# PMB.net
KiCad netlist of a schematic drawn in EAGLE
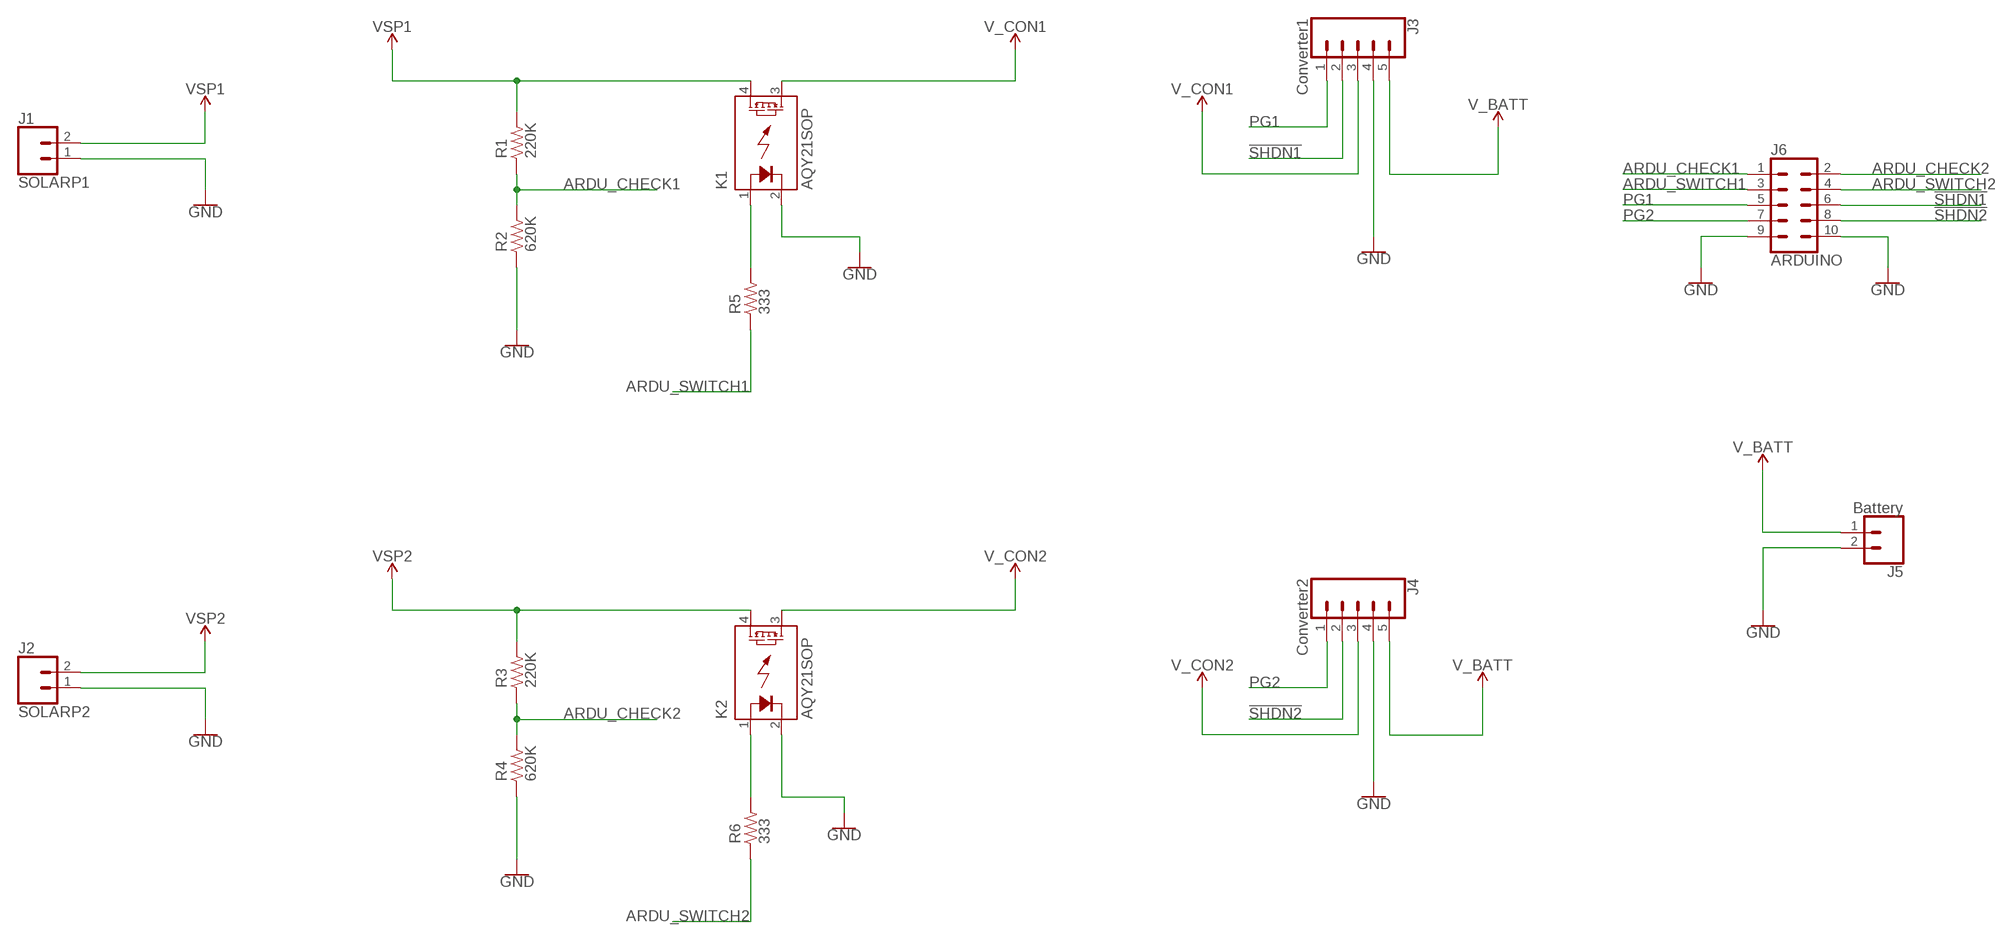
[diagram p0: schematic, sheet 1]

(export (version "E")
  (design (tool "Eeschema 10.0.6"))
  (components
    (comp (ref "J1")
      (value "SOLARP1")
      (footprint "eagle-import:1X02_LONGPADS")
      (libsource (lib "eagle-import") (part "CONN_02PTH3"))
    )
    (comp (ref "J2")
      (value "SOLARP2")
      (footprint "eagle-import:1X02_LONGPADS")
      (libsource (lib "eagle-import") (part "CONN_02PTH3"))
    )
    (comp (ref "J3")
      (value "Converter1")
      (footprint "eagle-import:1X05_LONGPADS")
      (libsource (lib "eagle-import") (part "CONN_05PTH_LONGPADS"))
    )
    (comp (ref "J4")
      (value "Converter2")
      (footprint "eagle-import:1X05_LONGPADS")
      (libsource (lib "eagle-import") (part "CONN_05PTH_LONGPADS"))
    )
    (comp (ref "J5")
      (value "Battery")
      (footprint "eagle-import:1X02_LOCK_LONGPADS")
      (libsource (lib "eagle-import") (part "CONN_02LOCK_LONGPADS"))
    )
    (comp (ref "J6")
      (value "ARDUINO")
      (footprint "eagle-import:2X5")
      (libsource (lib "eagle-import") (part "CONN_05X2PTH"))
    )
    (comp (ref "K1")
      (value "AQY21SOP")
      (footprint "eagle-import:SOP04")
      (libsource (lib "eagle-import") (part "AQYSOP21"))
    )
    (comp (ref "K2")
      (value "AQY21SOP")
      (footprint "eagle-import:SOP04")
      (libsource (lib "eagle-import") (part "AQYSOP21"))
    )
    (comp (ref "R1")
      (value "220K")
      (footprint "eagle-import:R1206")
      (libsource (lib "eagle-import") (part "R_1206"))
    )
    (comp (ref "R2")
      (value "620K")
      (footprint "eagle-import:R1206")
      (libsource (lib "eagle-import") (part "R_1206"))
    )
    (comp (ref "R3")
      (value "220K")
      (footprint "eagle-import:R1206")
      (libsource (lib "eagle-import") (part "R_1206"))
    )
    (comp (ref "R4")
      (value "620K")
      (footprint "eagle-import:R1206")
      (libsource (lib "eagle-import") (part "R_1206"))
    )
    (comp (ref "R5")
      (value "333")
      (footprint "eagle-import:R1206")
      (libsource (lib "eagle-import") (part "R_1206"))
    )
    (comp (ref "R6")
      (value "333")
      (footprint "eagle-import:R1206")
      (libsource (lib "eagle-import") (part "R_1206"))
    )
  )
  (nets
    (net (code "1") (name "/ARDU_CHECK1") (class "Default")
      (node (ref "J6") (pin "1") (pinfunction "1_1") (pintype "passive"))
      (node (ref "R1") (pin "1") (pinfunction "1_1") (pintype "passive"))
      (node (ref "R2") (pin "2") (pinfunction "2_2") (pintype "passive"))
    )
    (net (code "2") (name "/ARDU_CHECK2") (class "Default")
      (node (ref "J6") (pin "2") (pinfunction "2_2") (pintype "passive"))
      (node (ref "R3") (pin "1") (pinfunction "1_1") (pintype "passive"))
      (node (ref "R4") (pin "2") (pinfunction "2_2") (pintype "passive"))
    )
    (net (code "3") (name "/ARDU_SWITCH1") (class "Default")
      (node (ref "J6") (pin "3") (pinfunction "3_3") (pintype "passive"))
      (node (ref "R5") (pin "1") (pinfunction "1_1") (pintype "passive"))
    )
    (net (code "4") (name "/ARDU_SWITCH2") (class "Default")
      (node (ref "J6") (pin "4") (pinfunction "4_4") (pintype "passive"))
      (node (ref "R6") (pin "1") (pinfunction "1_1") (pintype "passive"))
    )
    (net (code "5") (name "/N$1") (class "Default")
      (node (ref "K1") (pin "1") (pinfunction "A_1") (pintype "passive"))
      (node (ref "K2") (pin "1") (pinfunction "A_1") (pintype "passive"))
      (node (ref "R5") (pin "2") (pinfunction "2_2") (pintype "passive"))
      (node (ref "R6") (pin "2") (pinfunction "2_2") (pintype "passive"))
    )
    (net (code "6") (name "/PG1") (class "Default")
      (node (ref "J3") (pin "1") (pinfunction "1_1") (pintype "passive"))
      (node (ref "J6") (pin "5") (pinfunction "5_5") (pintype "passive"))
    )
    (net (code "7") (name "/PG2") (class "Default")
      (node (ref "J4") (pin "1") (pinfunction "1_1") (pintype "passive"))
      (node (ref "J6") (pin "7") (pinfunction "7_7") (pintype "passive"))
    )
    (net (code "8") (name "/~{SHDN1}") (class "Default")
      (node (ref "J3") (pin "2") (pinfunction "2_2") (pintype "passive"))
      (node (ref "J6") (pin "6") (pinfunction "6_6") (pintype "passive"))
    )
    (net (code "9") (name "/~{SHDN2}") (class "Default")
      (node (ref "J4") (pin "2") (pinfunction "2_2") (pintype "passive"))
      (node (ref "J6") (pin "8") (pinfunction "8_8") (pintype "passive"))
    )
    (net (code "10") (name "GND") (class "Default")
      (node (ref "J1") (pin "1") (pinfunction "1_1") (pintype "passive"))
      (node (ref "J2") (pin "1") (pinfunction "1_1") (pintype "passive"))
      (node (ref "J3") (pin "4") (pinfunction "4_4") (pintype "passive"))
      (node (ref "J4") (pin "4") (pinfunction "4_4") (pintype "passive"))
      (node (ref "J5") (pin "2") (pinfunction "2_2") (pintype "passive"))
      (node (ref "J6") (pin "10") (pinfunction "10_10") (pintype "passive"))
      (node (ref "J6") (pin "9") (pinfunction "9_9") (pintype "passive"))
      (node (ref "K1") (pin "2") (pinfunction "K_2") (pintype "passive"))
      (node (ref "K2") (pin "2") (pinfunction "K_2") (pintype "passive"))
      (node (ref "R2") (pin "1") (pinfunction "1_1") (pintype "passive"))
      (node (ref "R4") (pin "1") (pinfunction "1_1") (pintype "passive"))
    )
    (net (code "11") (name "VSP1") (class "Default")
      (node (ref "J1") (pin "2") (pinfunction "2_2") (pintype "passive"))
      (node (ref "K1") (pin "4") (pinfunction "DS1_4") (pintype "passive"))
      (node (ref "R1") (pin "2") (pinfunction "2_2") (pintype "passive"))
    )
    (net (code "12") (name "VSP2") (class "Default")
      (node (ref "J2") (pin "2") (pinfunction "2_2") (pintype "passive"))
      (node (ref "K2") (pin "4") (pinfunction "DS1_4") (pintype "passive"))
      (node (ref "R3") (pin "2") (pinfunction "2_2") (pintype "passive"))
    )
    (net (code "13") (name "V_BATT") (class "Default")
      (node (ref "J3") (pin "5") (pinfunction "5_5") (pintype "passive"))
      (node (ref "J4") (pin "5") (pinfunction "5_5") (pintype "passive"))
      (node (ref "J5") (pin "1") (pinfunction "1_1") (pintype "passive"))
    )
    (net (code "14") (name "V_CON1") (class "Default")
      (node (ref "J3") (pin "3") (pinfunction "3_3") (pintype "passive"))
      (node (ref "K1") (pin "3") (pinfunction "DS2_3") (pintype "passive"))
    )
    (net (code "15") (name "V_CON2") (class "Default")
      (node (ref "J4") (pin "3") (pinfunction "3_3") (pintype "passive"))
      (node (ref "K2") (pin "3") (pinfunction "DS2_3") (pintype "passive"))
    )
  )
)
